# main_full_32.net
KiCad netlist of a schematic drawn in EAGLE
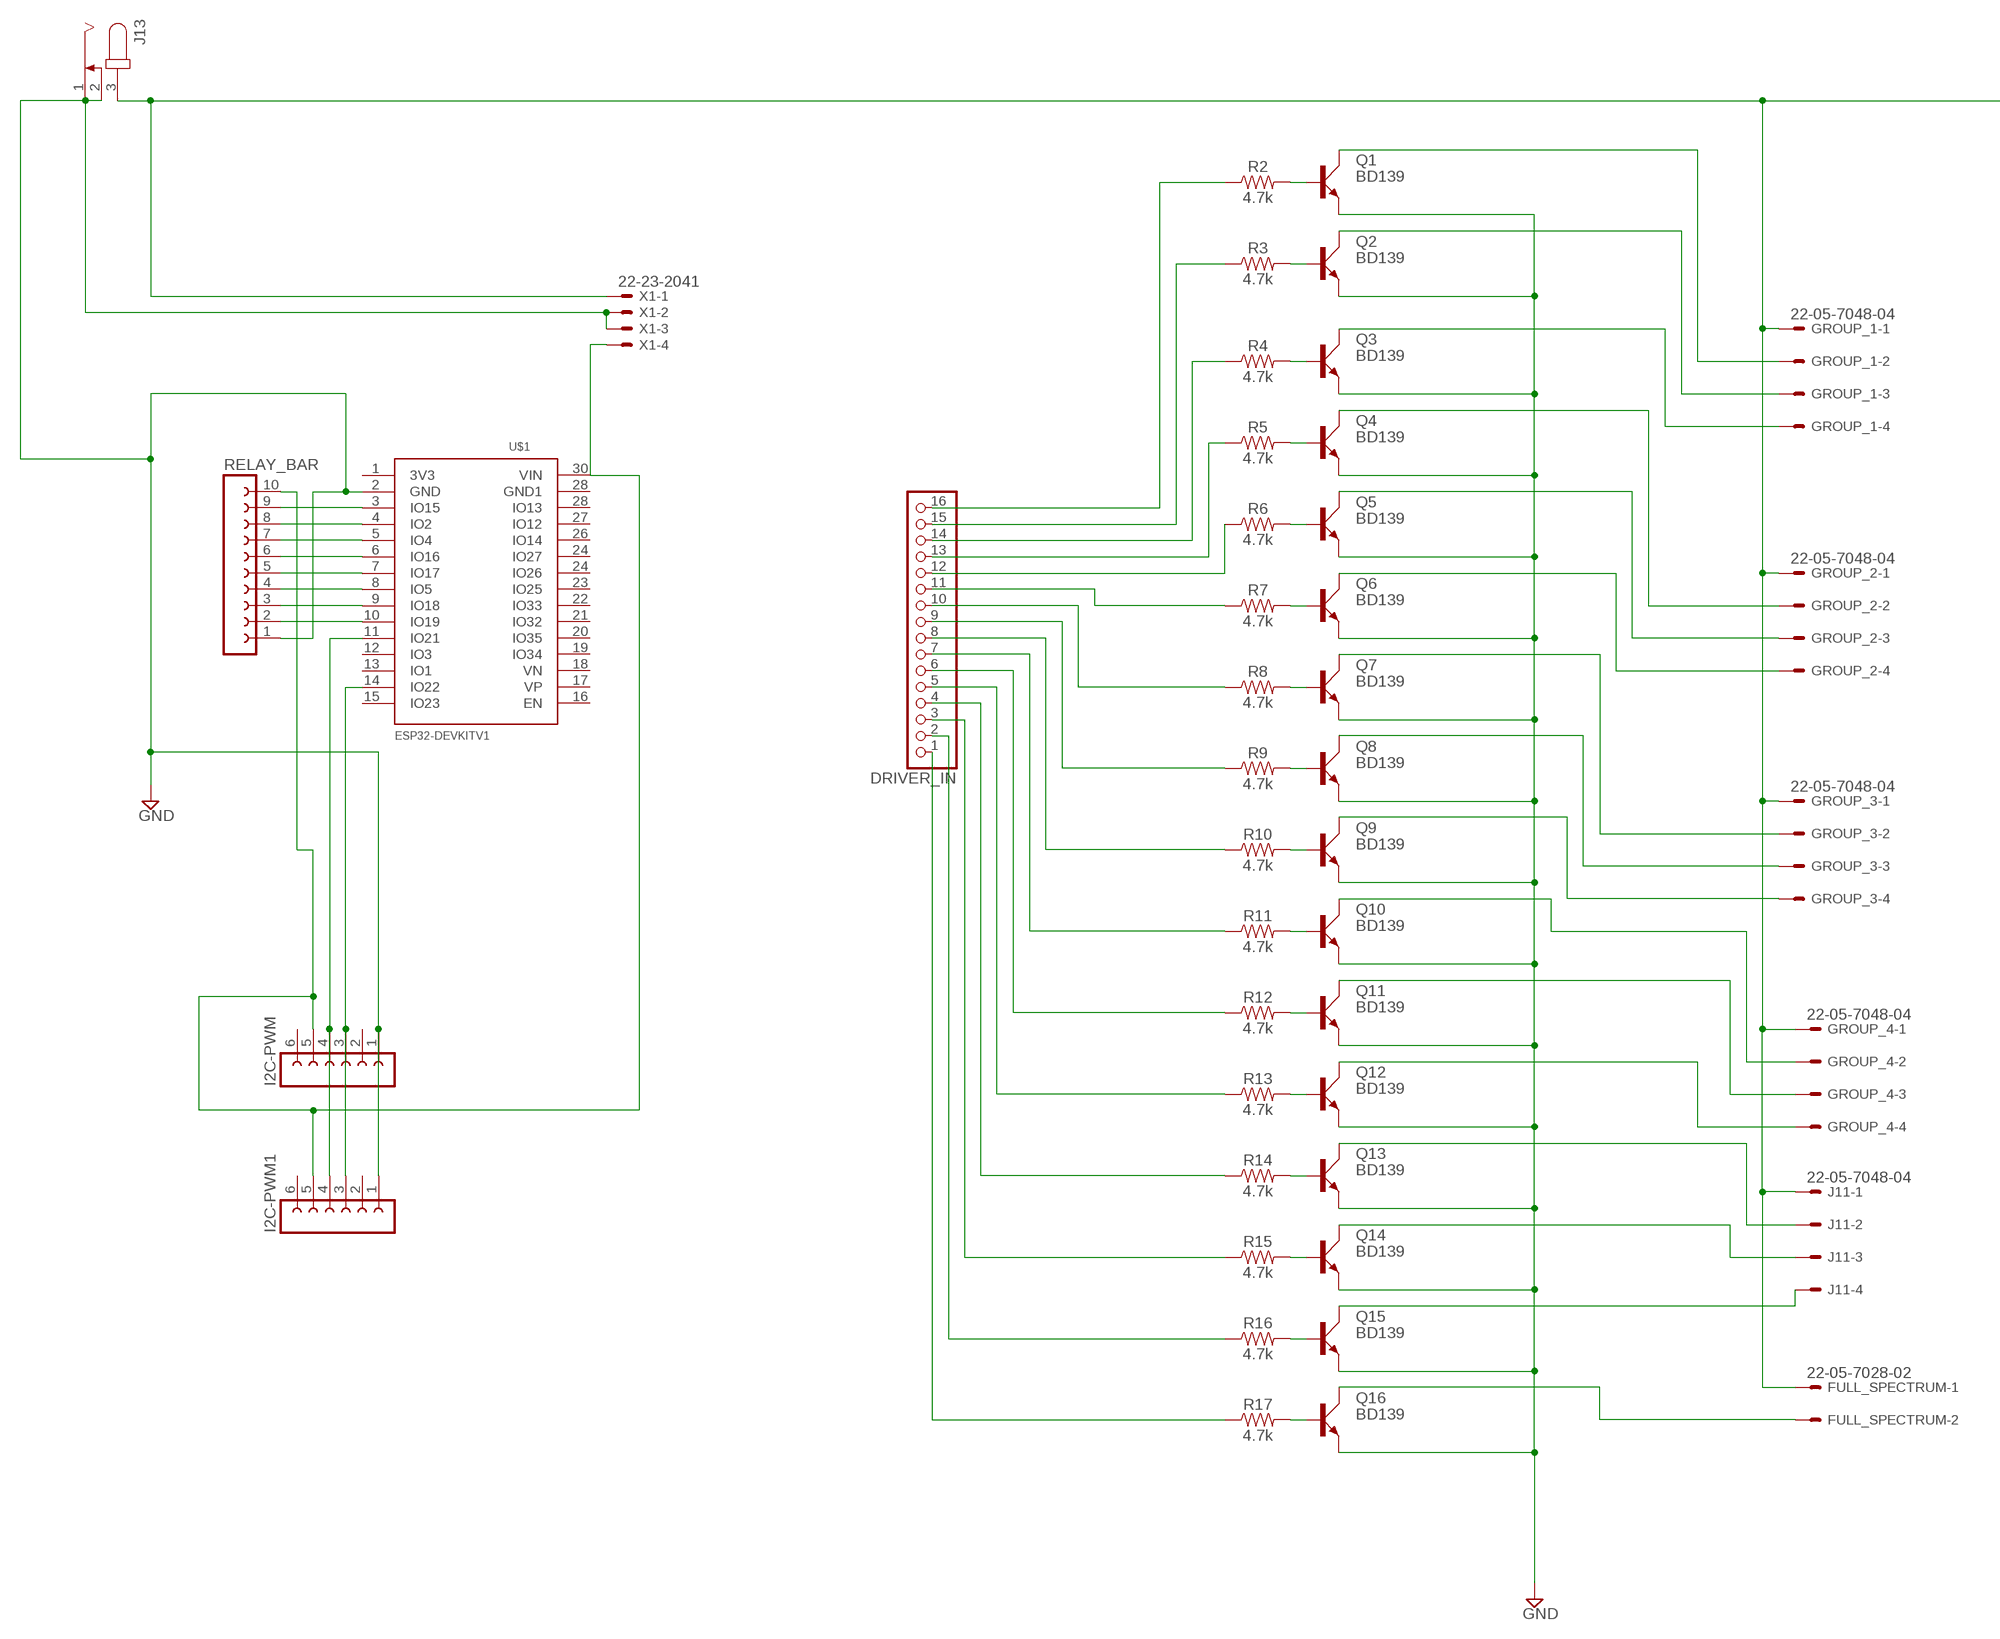
[diagram p0: schematic, sheet 1, part 1 of 2]
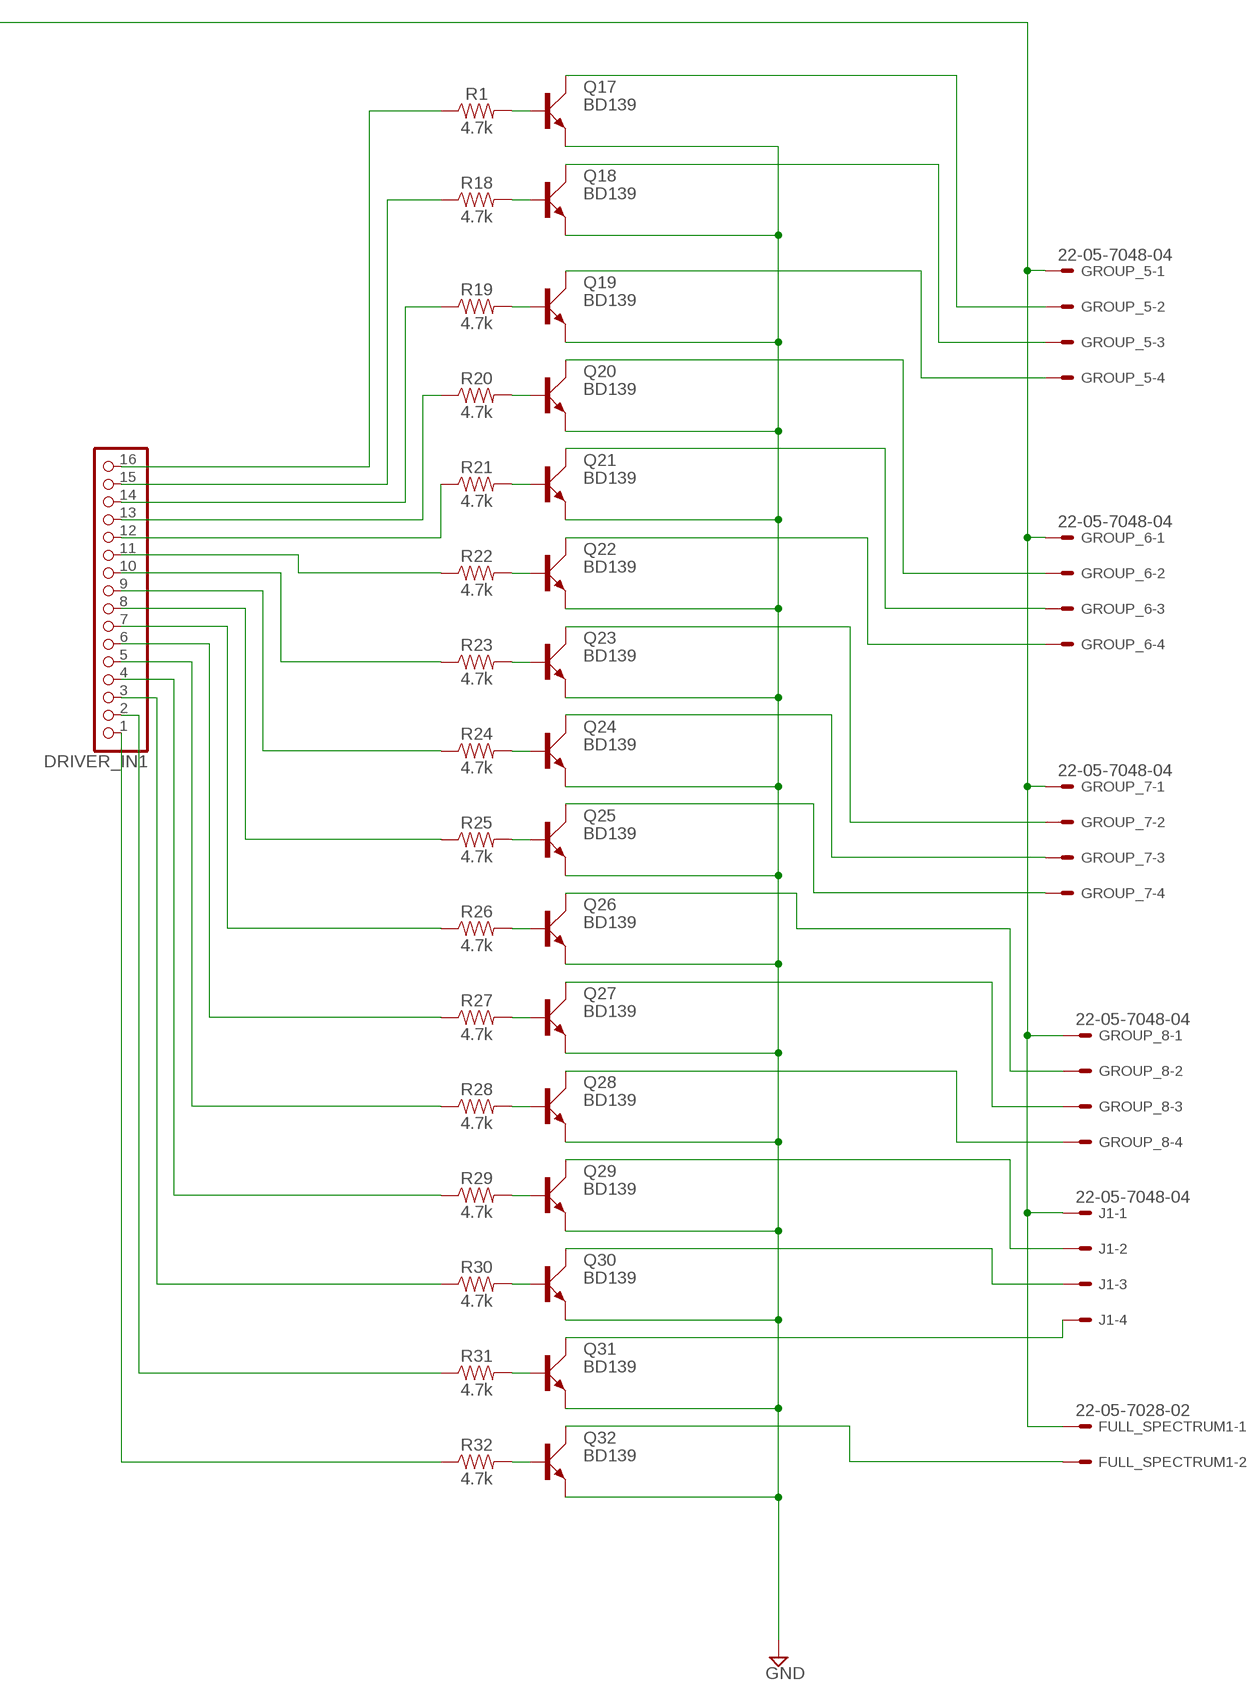
[diagram p1: schematic, sheet 1, part 2 of 2]

(export (version "E")
  (design (tool "Eeschema 10.0.6"))
  (components
    (comp (ref "DRIVER_IN")
      (value "PINHD-1X16/90")
      (footprint "eagle-import:1X16_90")
      (libsource (lib "eagle-import") (part "PINHD-1X16/90"))
    )
    (comp (ref "DRIVER_IN1")
      (value "PINHD-1X16/90")
      (footprint "eagle-import:1X16_90")
      (libsource (lib "eagle-import") (part "PINHD-1X16/90"))
    )
    (comp (ref "FULL_SPECTRUM")
      (value "22-05-7028-02")
      (footprint "eagle-import:7395-02")
      (fields (field (name "MF") "MOLEX"))
      (libsource (lib "eagle-import") (part "22-?-0205-7028"))
    )
    (comp (ref "FULL_SPECTRUM1")
      (value "22-05-7028-02")
      (footprint "eagle-import:7395-02")
      (fields (field (name "MF") "MOLEX"))
      (libsource (lib "eagle-import") (part "22-?-0205-7028"))
    )
    (comp (ref "GROUP_1")
      (value "22-05-7048-04")
      (footprint "eagle-import:7395-04")
      (fields (field (name "MF") "MOLEX"))
      (libsource (lib "eagle-import") (part "22-?-0405-7048"))
    )
    (comp (ref "GROUP_2")
      (value "22-05-7048-04")
      (footprint "eagle-import:7395-04")
      (fields (field (name "MF") "MOLEX"))
      (libsource (lib "eagle-import") (part "22-?-0405-7048"))
    )
    (comp (ref "GROUP_3")
      (value "22-05-7048-04")
      (footprint "eagle-import:7395-04")
      (fields (field (name "MF") "MOLEX"))
      (libsource (lib "eagle-import") (part "22-?-0405-7048"))
    )
    (comp (ref "GROUP_4")
      (value "22-05-7048-04")
      (footprint "eagle-import:7395-04")
      (fields (field (name "MF") "MOLEX"))
      (libsource (lib "eagle-import") (part "22-?-0405-7048"))
    )
    (comp (ref "GROUP_5")
      (value "22-05-7048-04")
      (footprint "eagle-import:7395-04")
      (fields (field (name "MF") "MOLEX"))
      (libsource (lib "eagle-import") (part "22-?-0405-7048"))
    )
    (comp (ref "GROUP_6")
      (value "22-05-7048-04")
      (footprint "eagle-import:7395-04")
      (fields (field (name "MF") "MOLEX"))
      (libsource (lib "eagle-import") (part "22-?-0405-7048"))
    )
    (comp (ref "GROUP_7")
      (value "22-05-7048-04")
      (footprint "eagle-import:7395-04")
      (fields (field (name "MF") "MOLEX"))
      (libsource (lib "eagle-import") (part "22-?-0405-7048"))
    )
    (comp (ref "GROUP_8")
      (value "22-05-7048-04")
      (footprint "eagle-import:7395-04")
      (fields (field (name "MF") "MOLEX"))
      (libsource (lib "eagle-import") (part "22-?-0405-7048"))
    )
    (comp (ref "I2C-PWM")
      (value "FE06W")
      (footprint "eagle-import:FE06W")
      (libsource (lib "eagle-import") (part "FE06W"))
    )
    (comp (ref "I2C-PWM1")
      (value "FE06W")
      (footprint "eagle-import:FE06W")
      (libsource (lib "eagle-import") (part "FE06W"))
    )
    (comp (ref "J1")
      (value "22-05-7048-04")
      (footprint "eagle-import:7395-04")
      (fields (field (name "MF") "MOLEX"))
      (libsource (lib "eagle-import") (part "22-?-0405-7048"))
    )
    (comp (ref "J11")
      (value "22-05-7048-04")
      (footprint "eagle-import:7395-04")
      (fields (field (name "MF") "MOLEX"))
      (libsource (lib "eagle-import") (part "22-?-0405-7048"))
    )
    (comp (ref "J13")
      (value "JACK-PLUG0")
      (footprint "eagle-import:SPC4077")
      (libsource (lib "eagle-import") (part "JACK-PLUG0"))
    )
    (comp (ref "Q1")
      (value "BD139")
      (footprint "eagle-import:TO126AV")
      (libsource (lib "eagle-import") (part "BD139"))
    )
    (comp (ref "Q2")
      (value "BD139")
      (footprint "eagle-import:TO126AV")
      (libsource (lib "eagle-import") (part "BD139"))
    )
    (comp (ref "Q3")
      (value "BD139")
      (footprint "eagle-import:TO126AV")
      (libsource (lib "eagle-import") (part "BD139"))
    )
    (comp (ref "Q4")
      (value "BD139")
      (footprint "eagle-import:TO126AV")
      (libsource (lib "eagle-import") (part "BD139"))
    )
    (comp (ref "Q5")
      (value "BD139")
      (footprint "eagle-import:TO126AV")
      (libsource (lib "eagle-import") (part "BD139"))
    )
    (comp (ref "Q6")
      (value "BD139")
      (footprint "eagle-import:TO126AV")
      (libsource (lib "eagle-import") (part "BD139"))
    )
    (comp (ref "Q7")
      (value "BD139")
      (footprint "eagle-import:TO126AV")
      (libsource (lib "eagle-import") (part "BD139"))
    )
    (comp (ref "Q8")
      (value "BD139")
      (footprint "eagle-import:TO126AV")
      (libsource (lib "eagle-import") (part "BD139"))
    )
    (comp (ref "Q9")
      (value "BD139")
      (footprint "eagle-import:TO126AV")
      (libsource (lib "eagle-import") (part "BD139"))
    )
    (comp (ref "Q10")
      (value "BD139")
      (footprint "eagle-import:TO126AV")
      (libsource (lib "eagle-import") (part "BD139"))
    )
    (comp (ref "Q11")
      (value "BD139")
      (footprint "eagle-import:TO126AV")
      (libsource (lib "eagle-import") (part "BD139"))
    )
    (comp (ref "Q12")
      (value "BD139")
      (footprint "eagle-import:TO126AV")
      (libsource (lib "eagle-import") (part "BD139"))
    )
    (comp (ref "Q13")
      (value "BD139")
      (footprint "eagle-import:TO126AV")
      (libsource (lib "eagle-import") (part "BD139"))
    )
    (comp (ref "Q14")
      (value "BD139")
      (footprint "eagle-import:TO126AV")
      (libsource (lib "eagle-import") (part "BD139"))
    )
    (comp (ref "Q15")
      (value "BD139")
      (footprint "eagle-import:TO126AV")
      (libsource (lib "eagle-import") (part "BD139"))
    )
    (comp (ref "Q16")
      (value "BD139")
      (footprint "eagle-import:TO126AV")
      (libsource (lib "eagle-import") (part "BD139"))
    )
    (comp (ref "Q17")
      (value "BD139")
      (footprint "eagle-import:TO126AV")
      (libsource (lib "eagle-import") (part "BD139"))
    )
    (comp (ref "Q18")
      (value "BD139")
      (footprint "eagle-import:TO126AV")
      (libsource (lib "eagle-import") (part "BD139"))
    )
    (comp (ref "Q19")
      (value "BD139")
      (footprint "eagle-import:TO126AV")
      (libsource (lib "eagle-import") (part "BD139"))
    )
    (comp (ref "Q20")
      (value "BD139")
      (footprint "eagle-import:TO126AV")
      (libsource (lib "eagle-import") (part "BD139"))
    )
    (comp (ref "Q21")
      (value "BD139")
      (footprint "eagle-import:TO126AV")
      (libsource (lib "eagle-import") (part "BD139"))
    )
    (comp (ref "Q22")
      (value "BD139")
      (footprint "eagle-import:TO126AV")
      (libsource (lib "eagle-import") (part "BD139"))
    )
    (comp (ref "Q23")
      (value "BD139")
      (footprint "eagle-import:TO126AV")
      (libsource (lib "eagle-import") (part "BD139"))
    )
    (comp (ref "Q24")
      (value "BD139")
      (footprint "eagle-import:TO126AV")
      (libsource (lib "eagle-import") (part "BD139"))
    )
    (comp (ref "Q25")
      (value "BD139")
      (footprint "eagle-import:TO126AV")
      (libsource (lib "eagle-import") (part "BD139"))
    )
    (comp (ref "Q26")
      (value "BD139")
      (footprint "eagle-import:TO126AV")
      (libsource (lib "eagle-import") (part "BD139"))
    )
    (comp (ref "Q27")
      (value "BD139")
      (footprint "eagle-import:TO126AV")
      (libsource (lib "eagle-import") (part "BD139"))
    )
    (comp (ref "Q28")
      (value "BD139")
      (footprint "eagle-import:TO126AV")
      (libsource (lib "eagle-import") (part "BD139"))
    )
    (comp (ref "Q29")
      (value "BD139")
      (footprint "eagle-import:TO126AV")
      (libsource (lib "eagle-import") (part "BD139"))
    )
    (comp (ref "Q30")
      (value "BD139")
      (footprint "eagle-import:TO126AV")
      (libsource (lib "eagle-import") (part "BD139"))
    )
    (comp (ref "Q31")
      (value "BD139")
      (footprint "eagle-import:TO126AV")
      (libsource (lib "eagle-import") (part "BD139"))
    )
    (comp (ref "Q32")
      (value "BD139")
      (footprint "eagle-import:TO126AV")
      (libsource (lib "eagle-import") (part "BD139"))
    )
    (comp (ref "R1")
      (value "4.7k")
      (footprint "eagle-import:0603")
      (libsource (lib "eagle-import") (part "4.7KOHM-0603-1/10W-1%"))
    )
    (comp (ref "R2")
      (value "4.7k")
      (footprint "eagle-import:0603")
      (libsource (lib "eagle-import") (part "4.7KOHM-0603-1/10W-1%"))
    )
    (comp (ref "R3")
      (value "4.7k")
      (footprint "eagle-import:0603")
      (libsource (lib "eagle-import") (part "4.7KOHM-0603-1/10W-1%"))
    )
    (comp (ref "R4")
      (value "4.7k")
      (footprint "eagle-import:0603")
      (libsource (lib "eagle-import") (part "4.7KOHM-0603-1/10W-1%"))
    )
    (comp (ref "R5")
      (value "4.7k")
      (footprint "eagle-import:0603")
      (libsource (lib "eagle-import") (part "4.7KOHM-0603-1/10W-1%"))
    )
    (comp (ref "R6")
      (value "4.7k")
      (footprint "eagle-import:0603")
      (libsource (lib "eagle-import") (part "4.7KOHM-0603-1/10W-1%"))
    )
    (comp (ref "R7")
      (value "4.7k")
      (footprint "eagle-import:0603")
      (libsource (lib "eagle-import") (part "4.7KOHM-0603-1/10W-1%"))
    )
    (comp (ref "R8")
      (value "4.7k")
      (footprint "eagle-import:0603")
      (libsource (lib "eagle-import") (part "4.7KOHM-0603-1/10W-1%"))
    )
    (comp (ref "R9")
      (value "4.7k")
      (footprint "eagle-import:0603")
      (libsource (lib "eagle-import") (part "4.7KOHM-0603-1/10W-1%"))
    )
    (comp (ref "R10")
      (value "4.7k")
      (footprint "eagle-import:0603")
      (libsource (lib "eagle-import") (part "4.7KOHM-0603-1/10W-1%"))
    )
    (comp (ref "R11")
      (value "4.7k")
      (footprint "eagle-import:0603")
      (libsource (lib "eagle-import") (part "4.7KOHM-0603-1/10W-1%"))
    )
    (comp (ref "R12")
      (value "4.7k")
      (footprint "eagle-import:0603")
      (libsource (lib "eagle-import") (part "4.7KOHM-0603-1/10W-1%"))
    )
    (comp (ref "R13")
      (value "4.7k")
      (footprint "eagle-import:0603")
      (libsource (lib "eagle-import") (part "4.7KOHM-0603-1/10W-1%"))
    )
    (comp (ref "R14")
      (value "4.7k")
      (footprint "eagle-import:0603")
      (libsource (lib "eagle-import") (part "4.7KOHM-0603-1/10W-1%"))
    )
    (comp (ref "R15")
      (value "4.7k")
      (footprint "eagle-import:0603")
      (libsource (lib "eagle-import") (part "4.7KOHM-0603-1/10W-1%"))
    )
    (comp (ref "R16")
      (value "4.7k")
      (footprint "eagle-import:0603")
      (libsource (lib "eagle-import") (part "4.7KOHM-0603-1/10W-1%"))
    )
    (comp (ref "R17")
      (value "4.7k")
      (footprint "eagle-import:0603")
      (libsource (lib "eagle-import") (part "4.7KOHM-0603-1/10W-1%"))
    )
    (comp (ref "R18")
      (value "4.7k")
      (footprint "eagle-import:0603")
      (libsource (lib "eagle-import") (part "4.7KOHM-0603-1/10W-1%"))
    )
    (comp (ref "R19")
      (value "4.7k")
      (footprint "eagle-import:0603")
      (libsource (lib "eagle-import") (part "4.7KOHM-0603-1/10W-1%"))
    )
    (comp (ref "R20")
      (value "4.7k")
      (footprint "eagle-import:0603")
      (libsource (lib "eagle-import") (part "4.7KOHM-0603-1/10W-1%"))
    )
    (comp (ref "R21")
      (value "4.7k")
      (footprint "eagle-import:0603")
      (libsource (lib "eagle-import") (part "4.7KOHM-0603-1/10W-1%"))
    )
    (comp (ref "R22")
      (value "4.7k")
      (footprint "eagle-import:0603")
      (libsource (lib "eagle-import") (part "4.7KOHM-0603-1/10W-1%"))
    )
    (comp (ref "R23")
      (value "4.7k")
      (footprint "eagle-import:0603")
      (libsource (lib "eagle-import") (part "4.7KOHM-0603-1/10W-1%"))
    )
    (comp (ref "R24")
      (value "4.7k")
      (footprint "eagle-import:0603")
      (libsource (lib "eagle-import") (part "4.7KOHM-0603-1/10W-1%"))
    )
    (comp (ref "R25")
      (value "4.7k")
      (footprint "eagle-import:0603")
      (libsource (lib "eagle-import") (part "4.7KOHM-0603-1/10W-1%"))
    )
    (comp (ref "R26")
      (value "4.7k")
      (footprint "eagle-import:0603")
      (libsource (lib "eagle-import") (part "4.7KOHM-0603-1/10W-1%"))
    )
    (comp (ref "R27")
      (value "4.7k")
      (footprint "eagle-import:0603")
      (libsource (lib "eagle-import") (part "4.7KOHM-0603-1/10W-1%"))
    )
    (comp (ref "R28")
      (value "4.7k")
      (footprint "eagle-import:0603")
      (libsource (lib "eagle-import") (part "4.7KOHM-0603-1/10W-1%"))
    )
    (comp (ref "R29")
      (value "4.7k")
      (footprint "eagle-import:0603")
      (libsource (lib "eagle-import") (part "4.7KOHM-0603-1/10W-1%"))
    )
    (comp (ref "R30")
      (value "4.7k")
      (footprint "eagle-import:0603")
      (libsource (lib "eagle-import") (part "4.7KOHM-0603-1/10W-1%"))
    )
    (comp (ref "R31")
      (value "4.7k")
      (footprint "eagle-import:0603")
      (libsource (lib "eagle-import") (part "4.7KOHM-0603-1/10W-1%"))
    )
    (comp (ref "R32")
      (value "4.7k")
      (footprint "eagle-import:0603")
      (libsource (lib "eagle-import") (part "4.7KOHM-0603-1/10W-1%"))
    )
    (comp (ref "RELAY_BAR")
      (value "FE10W")
      (footprint "eagle-import:FE10W")
      (libsource (lib "eagle-import") (part "FE10W"))
    )
    (comp (ref "U$1")
      (value "ESP32DEVKITV1")
      (footprint "eagle-import:ESP32-DEVKITV1")
      (libsource (lib "eagle-import") (part "ESP32DEVKITV1"))
    )
    (comp (ref "X1")
      (value "22-23-2041")
      (footprint "eagle-import:22-23-2041")
      (fields (field (name "MF") "MOLEX"))
      (libsource (lib "eagle-import") (part "22-23-2041"))
    )
  )
  (nets
    (net (code "1") (name "GND") (class "Default")
      (node (ref "I2C-PWM") (pin "1") (pinfunction "1_1") (pintype "passive"))
      (node (ref "I2C-PWM1") (pin "1") (pinfunction "1_1") (pintype "passive"))
      (node (ref "J13") (pin "1") (pinfunction "1_1") (pintype "passive"))
      (node (ref "J13") (pin "2") (pinfunction "2_2") (pintype "passive"))
      (node (ref "Q1") (pin "E") (pinfunction "E_E") (pintype "passive"))
      (node (ref "Q10") (pin "E") (pinfunction "E_E") (pintype "passive"))
      (node (ref "Q11") (pin "E") (pinfunction "E_E") (pintype "passive"))
      (node (ref "Q12") (pin "E") (pinfunction "E_E") (pintype "passive"))
      (node (ref "Q13") (pin "E") (pinfunction "E_E") (pintype "passive"))
      (node (ref "Q14") (pin "E") (pinfunction "E_E") (pintype "passive"))
      (node (ref "Q15") (pin "E") (pinfunction "E_E") (pintype "passive"))
      (node (ref "Q16") (pin "E") (pinfunction "E_E") (pintype "passive"))
      (node (ref "Q17") (pin "E") (pinfunction "E_E") (pintype "passive"))
      (node (ref "Q18") (pin "E") (pinfunction "E_E") (pintype "passive"))
      (node (ref "Q19") (pin "E") (pinfunction "E_E") (pintype "passive"))
      (node (ref "Q2") (pin "E") (pinfunction "E_E") (pintype "passive"))
      (node (ref "Q20") (pin "E") (pinfunction "E_E") (pintype "passive"))
      (node (ref "Q21") (pin "E") (pinfunction "E_E") (pintype "passive"))
      (node (ref "Q22") (pin "E") (pinfunction "E_E") (pintype "passive"))
      (node (ref "Q23") (pin "E") (pinfunction "E_E") (pintype "passive"))
      (node (ref "Q24") (pin "E") (pinfunction "E_E") (pintype "passive"))
      (node (ref "Q25") (pin "E") (pinfunction "E_E") (pintype "passive"))
      (node (ref "Q26") (pin "E") (pinfunction "E_E") (pintype "passive"))
      (node (ref "Q27") (pin "E") (pinfunction "E_E") (pintype "passive"))
      (node (ref "Q28") (pin "E") (pinfunction "E_E") (pintype "passive"))
      (node (ref "Q29") (pin "E") (pinfunction "E_E") (pintype "passive"))
      (node (ref "Q3") (pin "E") (pinfunction "E_E") (pintype "passive"))
      (node (ref "Q30") (pin "E") (pinfunction "E_E") (pintype "passive"))
      (node (ref "Q31") (pin "E") (pinfunction "E_E") (pintype "passive"))
      (node (ref "Q32") (pin "E") (pinfunction "E_E") (pintype "passive"))
      (node (ref "Q4") (pin "E") (pinfunction "E_E") (pintype "passive"))
      (node (ref "Q5") (pin "E") (pinfunction "E_E") (pintype "passive"))
      (node (ref "Q6") (pin "E") (pinfunction "E_E") (pintype "passive"))
      (node (ref "Q7") (pin "E") (pinfunction "E_E") (pintype "passive"))
      (node (ref "Q8") (pin "E") (pinfunction "E_E") (pintype "passive"))
      (node (ref "Q9") (pin "E") (pinfunction "E_E") (pintype "passive"))
      (node (ref "RELAY_BAR") (pin "1") (pinfunction "1_1") (pintype "passive"))
      (node (ref "U$1") (pin "2") (pinfunction "GND_2") (pintype "bidirectional"))
      (node (ref "X1") (pin "2") (pinfunction "S_2") (pintype "passive"))
      (node (ref "X1") (pin "3") (pinfunction "S_3") (pintype "passive"))
    )
    (net (code "2") (name "Net-(DRIVER_IN-Pad1)") (class "Default")
      (node (ref "DRIVER_IN") (pin "1") (pinfunction "1_1") (pintype "passive"))
      (node (ref "R17") (pin "1") (pinfunction "1_1") (pintype "passive"))
    )
    (net (code "3") (name "Net-(DRIVER_IN-Pad2)") (class "Default")
      (node (ref "DRIVER_IN") (pin "2") (pinfunction "2_2") (pintype "passive"))
      (node (ref "R16") (pin "1") (pinfunction "1_1") (pintype "passive"))
    )
    (net (code "4") (name "Net-(DRIVER_IN-Pad3)") (class "Default")
      (node (ref "DRIVER_IN") (pin "3") (pinfunction "3_3") (pintype "passive"))
      (node (ref "R15") (pin "1") (pinfunction "1_1") (pintype "passive"))
    )
    (net (code "5") (name "Net-(DRIVER_IN-Pad4)") (class "Default")
      (node (ref "DRIVER_IN") (pin "4") (pinfunction "4_4") (pintype "passive"))
      (node (ref "R14") (pin "1") (pinfunction "1_1") (pintype "passive"))
    )
    (net (code "6") (name "Net-(DRIVER_IN-Pad5)") (class "Default")
      (node (ref "DRIVER_IN") (pin "5") (pinfunction "5_5") (pintype "passive"))
      (node (ref "R13") (pin "1") (pinfunction "1_1") (pintype "passive"))
    )
    (net (code "7") (name "Net-(DRIVER_IN-Pad6)") (class "Default")
      (node (ref "DRIVER_IN") (pin "6") (pinfunction "6_6") (pintype "passive"))
      (node (ref "R12") (pin "1") (pinfunction "1_1") (pintype "passive"))
    )
    (net (code "8") (name "Net-(DRIVER_IN-Pad7)") (class "Default")
      (node (ref "DRIVER_IN") (pin "7") (pinfunction "7_7") (pintype "passive"))
      (node (ref "R11") (pin "1") (pinfunction "1_1") (pintype "passive"))
    )
    (net (code "9") (name "Net-(DRIVER_IN-Pad8)") (class "Default")
      (node (ref "DRIVER_IN") (pin "8") (pinfunction "8_8") (pintype "passive"))
      (node (ref "R10") (pin "1") (pinfunction "1_1") (pintype "passive"))
    )
    (net (code "10") (name "Net-(DRIVER_IN-Pad9)") (class "Default")
      (node (ref "DRIVER_IN") (pin "9") (pinfunction "9_9") (pintype "passive"))
      (node (ref "R9") (pin "1") (pinfunction "1_1") (pintype "passive"))
    )
    (net (code "11") (name "Net-(DRIVER_IN-Pad10)") (class "Default")
      (node (ref "DRIVER_IN") (pin "10") (pinfunction "10_10") (pintype "passive"))
      (node (ref "R8") (pin "1") (pinfunction "1_1") (pintype "passive"))
    )
    (net (code "12") (name "Net-(DRIVER_IN-Pad11)") (class "Default")
      (node (ref "DRIVER_IN") (pin "11") (pinfunction "11_11") (pintype "passive"))
      (node (ref "R7") (pin "1") (pinfunction "1_1") (pintype "passive"))
    )
    (net (code "13") (name "Net-(DRIVER_IN-Pad12)") (class "Default")
      (node (ref "DRIVER_IN") (pin "12") (pinfunction "12_12") (pintype "passive"))
      (node (ref "R6") (pin "1") (pinfunction "1_1") (pintype "passive"))
    )
    (net (code "14") (name "Net-(DRIVER_IN-Pad13)") (class "Default")
      (node (ref "DRIVER_IN") (pin "13") (pinfunction "13_13") (pintype "passive"))
      (node (ref "R5") (pin "1") (pinfunction "1_1") (pintype "passive"))
    )
    (net (code "15") (name "Net-(DRIVER_IN-Pad14)") (class "Default")
      (node (ref "DRIVER_IN") (pin "14") (pinfunction "14_14") (pintype "passive"))
      (node (ref "R4") (pin "1") (pinfunction "1_1") (pintype "passive"))
    )
    (net (code "16") (name "Net-(DRIVER_IN-Pad15)") (class "Default")
      (node (ref "DRIVER_IN") (pin "15") (pinfunction "15_15") (pintype "passive"))
      (node (ref "R3") (pin "1") (pinfunction "1_1") (pintype "passive"))
    )
    (net (code "17") (name "Net-(DRIVER_IN-Pad16)") (class "Default")
      (node (ref "DRIVER_IN") (pin "16") (pinfunction "16_16") (pintype "passive"))
      (node (ref "R2") (pin "1") (pinfunction "1_1") (pintype "passive"))
    )
    (net (code "18") (name "Net-(DRIVER_IN1-Pad1)") (class "Default")
      (node (ref "DRIVER_IN1") (pin "1") (pinfunction "1_1") (pintype "passive"))
      (node (ref "R32") (pin "1") (pinfunction "1_1") (pintype "passive"))
    )
    (net (code "19") (name "Net-(DRIVER_IN1-Pad2)") (class "Default")
      (node (ref "DRIVER_IN1") (pin "2") (pinfunction "2_2") (pintype "passive"))
      (node (ref "R31") (pin "1") (pinfunction "1_1") (pintype "passive"))
    )
    (net (code "20") (name "Net-(DRIVER_IN1-Pad3)") (class "Default")
      (node (ref "DRIVER_IN1") (pin "3") (pinfunction "3_3") (pintype "passive"))
      (node (ref "R30") (pin "1") (pinfunction "1_1") (pintype "passive"))
    )
    (net (code "21") (name "Net-(DRIVER_IN1-Pad4)") (class "Default")
      (node (ref "DRIVER_IN1") (pin "4") (pinfunction "4_4") (pintype "passive"))
      (node (ref "R29") (pin "1") (pinfunction "1_1") (pintype "passive"))
    )
    (net (code "22") (name "Net-(DRIVER_IN1-Pad5)") (class "Default")
      (node (ref "DRIVER_IN1") (pin "5") (pinfunction "5_5") (pintype "passive"))
      (node (ref "R28") (pin "1") (pinfunction "1_1") (pintype "passive"))
    )
    (net (code "23") (name "Net-(DRIVER_IN1-Pad6)") (class "Default")
      (node (ref "DRIVER_IN1") (pin "6") (pinfunction "6_6") (pintype "passive"))
      (node (ref "R27") (pin "1") (pinfunction "1_1") (pintype "passive"))
    )
    (net (code "24") (name "Net-(DRIVER_IN1-Pad7)") (class "Default")
      (node (ref "DRIVER_IN1") (pin "7") (pinfunction "7_7") (pintype "passive"))
      (node (ref "R26") (pin "1") (pinfunction "1_1") (pintype "passive"))
    )
    (net (code "25") (name "Net-(DRIVER_IN1-Pad8)") (class "Default")
      (node (ref "DRIVER_IN1") (pin "8") (pinfunction "8_8") (pintype "passive"))
      (node (ref "R25") (pin "1") (pinfunction "1_1") (pintype "passive"))
    )
    (net (code "26") (name "Net-(DRIVER_IN1-Pad9)") (class "Default")
      (node (ref "DRIVER_IN1") (pin "9") (pinfunction "9_9") (pintype "passive"))
      (node (ref "R24") (pin "1") (pinfunction "1_1") (pintype "passive"))
    )
    (net (code "27") (name "Net-(DRIVER_IN1-Pad10)") (class "Default")
      (node (ref "DRIVER_IN1") (pin "10") (pinfunction "10_10") (pintype "passive"))
      (node (ref "R23") (pin "1") (pinfunction "1_1") (pintype "passive"))
    )
    (net (code "28") (name "Net-(DRIVER_IN1-Pad11)") (class "Default")
      (node (ref "DRIVER_IN1") (pin "11") (pinfunction "11_11") (pintype "passive"))
      (node (ref "R22") (pin "1") (pinfunction "1_1") (pintype "passive"))
    )
    (net (code "29") (name "Net-(DRIVER_IN1-Pad12)") (class "Default")
      (node (ref "DRIVER_IN1") (pin "12") (pinfunction "12_12") (pintype "passive"))
      (node (ref "R21") (pin "1") (pinfunction "1_1") (pintype "passive"))
    )
    (net (code "30") (name "Net-(DRIVER_IN1-Pad13)") (class "Default")
      (node (ref "DRIVER_IN1") (pin "13") (pinfunction "13_13") (pintype "passive"))
      (node (ref "R20") (pin "1") (pinfunction "1_1") (pintype "passive"))
    )
    (net (code "31") (name "Net-(DRIVER_IN1-Pad14)") (class "Default")
      (node (ref "DRIVER_IN1") (pin "14") (pinfunction "14_14") (pintype "passive"))
      (node (ref "R19") (pin "1") (pinfunction "1_1") (pintype "passive"))
    )
    (net (code "32") (name "Net-(DRIVER_IN1-Pad15)") (class "Default")
      (node (ref "DRIVER_IN1") (pin "15") (pinfunction "15_15") (pintype "passive"))
      (node (ref "R18") (pin "1") (pinfunction "1_1") (pintype "passive"))
    )
    (net (code "33") (name "Net-(DRIVER_IN1-Pad16)") (class "Default")
      (node (ref "DRIVER_IN1") (pin "16") (pinfunction "16_16") (pintype "passive"))
      (node (ref "R1") (pin "1") (pinfunction "1_1") (pintype "passive"))
    )
    (net (code "34") (name "Net-(FULL_SPECTRUM1A-S)") (class "Default")
      (node (ref "FULL_SPECTRUM") (pin "1") (pinfunction "S_1") (pintype "passive"))
      (node (ref "FULL_SPECTRUM1") (pin "1") (pinfunction "S_1") (pintype "passive"))
      (node (ref "GROUP_1") (pin "1") (pinfunction "S_1") (pintype "passive"))
      (node (ref "GROUP_2") (pin "1") (pinfunction "S_1") (pintype "passive"))
      (node (ref "GROUP_3") (pin "1") (pinfunction "S_1") (pintype "passive"))
      (node (ref "GROUP_4") (pin "1") (pinfunction "S_1") (pintype "passive"))
      (node (ref "GROUP_5") (pin "1") (pinfunction "S_1") (pintype "passive"))
      (node (ref "GROUP_6") (pin "1") (pinfunction "S_1") (pintype "passive"))
      (node (ref "GROUP_7") (pin "1") (pinfunction "S_1") (pintype "passive"))
      (node (ref "GROUP_8") (pin "1") (pinfunction "S_1") (pintype "passive"))
      (node (ref "J1") (pin "1") (pinfunction "S_1") (pintype "passive"))
      (node (ref "J11") (pin "1") (pinfunction "S_1") (pintype "passive"))
      (node (ref "J13") (pin "3") (pinfunction "3_3") (pintype "passive"))
      (node (ref "X1") (pin "1") (pinfunction "S_1") (pintype "passive"))
    )
    (net (code "35") (name "Net-(FULL_SPECTRUM1B-S)") (class "Default")
      (node (ref "FULL_SPECTRUM1") (pin "2") (pinfunction "S_2") (pintype "passive"))
      (node (ref "Q32") (pin "C") (pinfunction "C_C") (pintype "passive"))
    )
    (net (code "36") (name "Net-(FULL_SPECTRUMB-S)") (class "Default")
      (node (ref "FULL_SPECTRUM") (pin "2") (pinfunction "S_2") (pintype "passive"))
      (node (ref "Q16") (pin "C") (pinfunction "C_C") (pintype "passive"))
    )
    (net (code "37") (name "Net-(GROUP_1B-S)") (class "Default")
      (node (ref "GROUP_1") (pin "2") (pinfunction "S_2") (pintype "passive"))
      (node (ref "Q1") (pin "C") (pinfunction "C_C") (pintype "passive"))
    )
    (net (code "38") (name "Net-(GROUP_1C-S)") (class "Default")
      (node (ref "GROUP_1") (pin "3") (pinfunction "S_3") (pintype "passive"))
      (node (ref "Q2") (pin "C") (pinfunction "C_C") (pintype "passive"))
    )
    (net (code "39") (name "Net-(GROUP_1D-S)") (class "Default")
      (node (ref "GROUP_1") (pin "4") (pinfunction "S_4") (pintype "passive"))
      (node (ref "Q3") (pin "C") (pinfunction "C_C") (pintype "passive"))
    )
    (net (code "40") (name "Net-(GROUP_2B-S)") (class "Default")
      (node (ref "GROUP_2") (pin "2") (pinfunction "S_2") (pintype "passive"))
      (node (ref "Q4") (pin "C") (pinfunction "C_C") (pintype "passive"))
    )
    (net (code "41") (name "Net-(GROUP_2C-S)") (class "Default")
      (node (ref "GROUP_2") (pin "3") (pinfunction "S_3") (pintype "passive"))
      (node (ref "Q5") (pin "C") (pinfunction "C_C") (pintype "passive"))
    )
    (net (code "42") (name "Net-(GROUP_2D-S)") (class "Default")
      (node (ref "GROUP_2") (pin "4") (pinfunction "S_4") (pintype "passive"))
      (node (ref "Q6") (pin "C") (pinfunction "C_C") (pintype "passive"))
    )
    (net (code "43") (name "Net-(GROUP_3B-S)") (class "Default")
      (node (ref "GROUP_3") (pin "2") (pinfunction "S_2") (pintype "passive"))
      (node (ref "Q7") (pin "C") (pinfunction "C_C") (pintype "passive"))
    )
    (net (code "44") (name "Net-(GROUP_3C-S)") (class "Default")
      (node (ref "GROUP_3") (pin "3") (pinfunction "S_3") (pintype "passive"))
      (node (ref "Q8") (pin "C") (pinfunction "C_C") (pintype "passive"))
    )
    (net (code "45") (name "Net-(GROUP_3D-S)") (class "Default")
      (node (ref "GROUP_3") (pin "4") (pinfunction "S_4") (pintype "passive"))
      (node (ref "Q9") (pin "C") (pinfunction "C_C") (pintype "passive"))
    )
    (net (code "46") (name "Net-(GROUP_4B-S)") (class "Default")
      (node (ref "GROUP_4") (pin "2") (pinfunction "S_2") (pintype "passive"))
      (node (ref "Q10") (pin "C") (pinfunction "C_C") (pintype "passive"))
    )
    (net (code "47") (name "Net-(GROUP_4C-S)") (class "Default")
      (node (ref "GROUP_4") (pin "3") (pinfunction "S_3") (pintype "passive"))
      (node (ref "Q11") (pin "C") (pinfunction "C_C") (pintype "passive"))
    )
    (net (code "48") (name "Net-(GROUP_4D-S)") (class "Default")
      (node (ref "GROUP_4") (pin "4") (pinfunction "S_4") (pintype "passive"))
      (node (ref "Q12") (pin "C") (pinfunction "C_C") (pintype "passive"))
    )
    (net (code "49") (name "Net-(GROUP_5B-S)") (class "Default")
      (node (ref "GROUP_5") (pin "2") (pinfunction "S_2") (pintype "passive"))
      (node (ref "Q17") (pin "C") (pinfunction "C_C") (pintype "passive"))
    )
    (net (code "50") (name "Net-(GROUP_5C-S)") (class "Default")
      (node (ref "GROUP_5") (pin "3") (pinfunction "S_3") (pintype "passive"))
      (node (ref "Q18") (pin "C") (pinfunction "C_C") (pintype "passive"))
    )
    (net (code "51") (name "Net-(GROUP_5D-S)") (class "Default")
      (node (ref "GROUP_5") (pin "4") (pinfunction "S_4") (pintype "passive"))
      (node (ref "Q19") (pin "C") (pinfunction "C_C") (pintype "passive"))
    )
    (net (code "52") (name "Net-(GROUP_6B-S)") (class "Default")
      (node (ref "GROUP_6") (pin "2") (pinfunction "S_2") (pintype "passive"))
      (node (ref "Q20") (pin "C") (pinfunction "C_C") (pintype "passive"))
    )
    (net (code "53") (name "Net-(GROUP_6C-S)") (class "Default")
      (node (ref "GROUP_6") (pin "3") (pinfunction "S_3") (pintype "passive"))
      (node (ref "Q21") (pin "C") (pinfunction "C_C") (pintype "passive"))
    )
    (net (code "54") (name "Net-(GROUP_6D-S)") (class "Default")
      (node (ref "GROUP_6") (pin "4") (pinfunction "S_4") (pintype "passive"))
      (node (ref "Q22") (pin "C") (pinfunction "C_C") (pintype "passive"))
    )
    (net (code "55") (name "Net-(GROUP_7B-S)") (class "Default")
      (node (ref "GROUP_7") (pin "2") (pinfunction "S_2") (pintype "passive"))
      (node (ref "Q23") (pin "C") (pinfunction "C_C") (pintype "passive"))
    )
    (net (code "56") (name "Net-(GROUP_7C-S)") (class "Default")
      (node (ref "GROUP_7") (pin "3") (pinfunction "S_3") (pintype "passive"))
      (node (ref "Q24") (pin "C") (pinfunction "C_C") (pintype "passive"))
    )
    (net (code "57") (name "Net-(GROUP_7D-S)") (class "Default")
      (node (ref "GROUP_7") (pin "4") (pinfunction "S_4") (pintype "passive"))
      (node (ref "Q25") (pin "C") (pinfunction "C_C") (pintype "passive"))
    )
    (net (code "58") (name "Net-(GROUP_8B-S)") (class "Default")
      (node (ref "GROUP_8") (pin "2") (pinfunction "S_2") (pintype "passive"))
      (node (ref "Q26") (pin "C") (pinfunction "C_C") (pintype "passive"))
    )
    (net (code "59") (name "Net-(GROUP_8C-S)") (class "Default")
      (node (ref "GROUP_8") (pin "3") (pinfunction "S_3") (pintype "passive"))
      (node (ref "Q27") (pin "C") (pinfunction "C_C") (pintype "passive"))
    )
    (net (code "60") (name "Net-(GROUP_8D-S)") (class "Default")
      (node (ref "GROUP_8") (pin "4") (pinfunction "S_4") (pintype "passive"))
      (node (ref "Q28") (pin "C") (pinfunction "C_C") (pintype "passive"))
    )
    (net (code "61") (name "Net-(J1B-S)") (class "Default")
      (node (ref "J1") (pin "2") (pinfunction "S_2") (pintype "passive"))
      (node (ref "Q29") (pin "C") (pinfunction "C_C") (pintype "passive"))
    )
    (net (code "62") (name "Net-(J1C-S)") (class "Default")
      (node (ref "J1") (pin "3") (pinfunction "S_3") (pintype "passive"))
      (node (ref "Q30") (pin "C") (pinfunction "C_C") (pintype "passive"))
    )
    (net (code "63") (name "Net-(J1D-S)") (class "Default")
      (node (ref "J1") (pin "4") (pinfunction "S_4") (pintype "passive"))
      (node (ref "Q31") (pin "C") (pinfunction "C_C") (pintype "passive"))
    )
    (net (code "64") (name "Net-(J11B-S)") (class "Default")
      (node (ref "J11") (pin "2") (pinfunction "S_2") (pintype "passive"))
      (node (ref "Q13") (pin "C") (pinfunction "C_C") (pintype "passive"))
    )
    (net (code "65") (name "Net-(J11C-S)") (class "Default")
      (node (ref "J11") (pin "3") (pinfunction "S_3") (pintype "passive"))
      (node (ref "Q14") (pin "C") (pinfunction "C_C") (pintype "passive"))
    )
    (net (code "66") (name "Net-(J11D-S)") (class "Default")
      (node (ref "J11") (pin "4") (pinfunction "S_4") (pintype "passive"))
      (node (ref "Q15") (pin "C") (pinfunction "C_C") (pintype "passive"))
    )
    (net (code "67") (name "Net-(Q1-PadB)") (class "Default")
      (node (ref "Q1") (pin "B") (pinfunction "B_B") (pintype "passive"))
      (node (ref "R2") (pin "2") (pinfunction "2_2") (pintype "passive"))
    )
    (net (code "68") (name "Net-(Q2-PadB)") (class "Default")
      (node (ref "Q2") (pin "B") (pinfunction "B_B") (pintype "passive"))
      (node (ref "R3") (pin "2") (pinfunction "2_2") (pintype "passive"))
    )
    (net (code "69") (name "Net-(Q3-PadB)") (class "Default")
      (node (ref "Q3") (pin "B") (pinfunction "B_B") (pintype "passive"))
      (node (ref "R4") (pin "2") (pinfunction "2_2") (pintype "passive"))
    )
    (net (code "70") (name "Net-(Q4-PadB)") (class "Default")
      (node (ref "Q4") (pin "B") (pinfunction "B_B") (pintype "passive"))
      (node (ref "R5") (pin "2") (pinfunction "2_2") (pintype "passive"))
    )
    (net (code "71") (name "Net-(Q5-PadB)") (class "Default")
      (node (ref "Q5") (pin "B") (pinfunction "B_B") (pintype "passive"))
      (node (ref "R6") (pin "2") (pinfunction "2_2") (pintype "passive"))
    )
    (net (code "72") (name "Net-(Q6-PadB)") (class "Default")
      (node (ref "Q6") (pin "B") (pinfunction "B_B") (pintype "passive"))
      (node (ref "R7") (pin "2") (pinfunction "2_2") (pintype "passive"))
    )
    (net (code "73") (name "Net-(Q7-PadB)") (class "Default")
      (node (ref "Q7") (pin "B") (pinfunction "B_B") (pintype "passive"))
      (node (ref "R8") (pin "2") (pinfunction "2_2") (pintype "passive"))
    )
    (net (code "74") (name "Net-(Q8-PadB)") (class "Default")
      (node (ref "Q8") (pin "B") (pinfunction "B_B") (pintype "passive"))
      (node (ref "R9") (pin "2") (pinfunction "2_2") (pintype "passive"))
    )
    (net (code "75") (name "Net-(Q9-PadB)") (class "Default")
      (node (ref "Q9") (pin "B") (pinfunction "B_B") (pintype "passive"))
      (node (ref "R10") (pin "2") (pinfunction "2_2") (pintype "passive"))
    )
    (net (code "76") (name "Net-(Q10-PadB)") (class "Default")
      (node (ref "Q10") (pin "B") (pinfunction "B_B") (pintype "passive"))
      (node (ref "R11") (pin "2") (pinfunction "2_2") (pintype "passive"))
    )
    (net (code "77") (name "Net-(Q11-PadB)") (class "Default")
      (node (ref "Q11") (pin "B") (pinfunction "B_B") (pintype "passive"))
      (node (ref "R12") (pin "2") (pinfunction "2_2") (pintype "passive"))
    )
    (net (code "78") (name "Net-(Q12-PadB)") (class "Default")
      (node (ref "Q12") (pin "B") (pinfunction "B_B") (pintype "passive"))
      (node (ref "R13") (pin "2") (pinfunction "2_2") (pintype "passive"))
    )
    (net (code "79") (name "Net-(Q13-PadB)") (class "Default")
      (node (ref "Q13") (pin "B") (pinfunction "B_B") (pintype "passive"))
      (node (ref "R14") (pin "2") (pinfunction "2_2") (pintype "passive"))
    )
    (net (code "80") (name "Net-(Q14-PadB)") (class "Default")
      (node (ref "Q14") (pin "B") (pinfunction "B_B") (pintype "passive"))
      (node (ref "R15") (pin "2") (pinfunction "2_2") (pintype "passive"))
    )
    (net (code "81") (name "Net-(Q15-PadB)") (class "Default")
      (node (ref "Q15") (pin "B") (pinfunction "B_B") (pintype "passive"))
      (node (ref "R16") (pin "2") (pinfunction "2_2") (pintype "passive"))
    )
    (net (code "82") (name "Net-(Q16-PadB)") (class "Default")
      (node (ref "Q16") (pin "B") (pinfunction "B_B") (pintype "passive"))
      (node (ref "R17") (pin "2") (pinfunction "2_2") (pintype "passive"))
    )
    (net (code "83") (name "Net-(Q17-PadB)") (class "Default")
      (node (ref "Q17") (pin "B") (pinfunction "B_B") (pintype "passive"))
      (node (ref "R1") (pin "2") (pinfunction "2_2") (pintype "passive"))
    )
    (net (code "84") (name "Net-(Q18-PadB)") (class "Default")
      (node (ref "Q18") (pin "B") (pinfunction "B_B") (pintype "passive"))
      (node (ref "R18") (pin "2") (pinfunction "2_2") (pintype "passive"))
    )
    (net (code "85") (name "Net-(Q19-PadB)") (class "Default")
      (node (ref "Q19") (pin "B") (pinfunction "B_B") (pintype "passive"))
      (node (ref "R19") (pin "2") (pinfunction "2_2") (pintype "passive"))
    )
    (net (code "86") (name "Net-(Q20-PadB)") (class "Default")
      (node (ref "Q20") (pin "B") (pinfunction "B_B") (pintype "passive"))
      (node (ref "R20") (pin "2") (pinfunction "2_2") (pintype "passive"))
    )
    (net (code "87") (name "Net-(Q21-PadB)") (class "Default")
      (node (ref "Q21") (pin "B") (pinfunction "B_B") (pintype "passive"))
      (node (ref "R21") (pin "2") (pinfunction "2_2") (pintype "passive"))
    )
    (net (code "88") (name "Net-(Q22-PadB)") (class "Default")
      (node (ref "Q22") (pin "B") (pinfunction "B_B") (pintype "passive"))
      (node (ref "R22") (pin "2") (pinfunction "2_2") (pintype "passive"))
    )
    (net (code "89") (name "Net-(Q23-PadB)") (class "Default")
      (node (ref "Q23") (pin "B") (pinfunction "B_B") (pintype "passive"))
      (node (ref "R23") (pin "2") (pinfunction "2_2") (pintype "passive"))
    )
    (net (code "90") (name "Net-(Q24-PadB)") (class "Default")
      (node (ref "Q24") (pin "B") (pinfunction "B_B") (pintype "passive"))
      (node (ref "R24") (pin "2") (pinfunction "2_2") (pintype "passive"))
    )
    (net (code "91") (name "Net-(Q25-PadB)") (class "Default")
      (node (ref "Q25") (pin "B") (pinfunction "B_B") (pintype "passive"))
      (node (ref "R25") (pin "2") (pinfunction "2_2") (pintype "passive"))
    )
    (net (code "92") (name "Net-(Q26-PadB)") (class "Default")
      (node (ref "Q26") (pin "B") (pinfunction "B_B") (pintype "passive"))
      (node (ref "R26") (pin "2") (pinfunction "2_2") (pintype "passive"))
    )
    (net (code "93") (name "Net-(Q27-PadB)") (class "Default")
      (node (ref "Q27") (pin "B") (pinfunction "B_B") (pintype "passive"))
      (node (ref "R27") (pin "2") (pinfunction "2_2") (pintype "passive"))
    )
    (net (code "94") (name "Net-(Q28-PadB)") (class "Default")
      (node (ref "Q28") (pin "B") (pinfunction "B_B") (pintype "passive"))
      (node (ref "R28") (pin "2") (pinfunction "2_2") (pintype "passive"))
    )
    (net (code "95") (name "Net-(Q29-PadB)") (class "Default")
      (node (ref "Q29") (pin "B") (pinfunction "B_B") (pintype "passive"))
      (node (ref "R29") (pin "2") (pinfunction "2_2") (pintype "passive"))
    )
    (net (code "96") (name "Net-(Q30-PadB)") (class "Default")
      (node (ref "Q30") (pin "B") (pinfunction "B_B") (pintype "passive"))
      (node (ref "R30") (pin "2") (pinfunction "2_2") (pintype "passive"))
    )
    (net (code "97") (name "Net-(Q31-PadB)") (class "Default")
      (node (ref "Q31") (pin "B") (pinfunction "B_B") (pintype "passive"))
      (node (ref "R31") (pin "2") (pinfunction "2_2") (pintype "passive"))
    )
    (net (code "98") (name "Net-(Q32-PadB)") (class "Default")
      (node (ref "Q32") (pin "B") (pinfunction "B_B") (pintype "passive"))
      (node (ref "R32") (pin "2") (pinfunction "2_2") (pintype "passive"))
    )
    (net (code "99") (name "Net-(U$1-IO2)") (class "Default")
      (node (ref "RELAY_BAR") (pin "8") (pinfunction "8_8") (pintype "passive"))
      (node (ref "U$1") (pin "4") (pinfunction "IO2_4") (pintype "bidirectional"))
    )
    (net (code "100") (name "Net-(U$1-IO4)") (class "Default")
      (node (ref "RELAY_BAR") (pin "7") (pinfunction "7_7") (pintype "passive"))
      (node (ref "U$1") (pin "5") (pinfunction "IO4_5") (pintype "bidirectional"))
    )
    (net (code "101") (name "Net-(U$1-IO5)") (class "Default")
      (node (ref "RELAY_BAR") (pin "4") (pinfunction "4_4") (pintype "passive"))
      (node (ref "U$1") (pin "8") (pinfunction "IO5_8") (pintype "bidirectional"))
    )
    (net (code "102") (name "Net-(U$1-IO15)") (class "Default")
      (node (ref "RELAY_BAR") (pin "9") (pinfunction "9_9") (pintype "passive"))
      (node (ref "U$1") (pin "3") (pinfunction "IO15_3") (pintype "bidirectional"))
    )
    (net (code "103") (name "Net-(U$1-IO16)") (class "Default")
      (node (ref "RELAY_BAR") (pin "6") (pinfunction "6_6") (pintype "passive"))
      (node (ref "U$1") (pin "6") (pinfunction "IO16_6") (pintype "bidirectional"))
    )
    (net (code "104") (name "Net-(U$1-IO17)") (class "Default")
      (node (ref "RELAY_BAR") (pin "5") (pinfunction "5_5") (pintype "passive"))
      (node (ref "U$1") (pin "7") (pinfunction "IO17_7") (pintype "bidirectional"))
    )
    (net (code "105") (name "Net-(U$1-IO18)") (class "Default")
      (node (ref "RELAY_BAR") (pin "3") (pinfunction "3_3") (pintype "passive"))
      (node (ref "U$1") (pin "9") (pinfunction "IO18_9") (pintype "bidirectional"))
    )
    (net (code "106") (name "Net-(U$1-IO19)") (class "Default")
      (node (ref "RELAY_BAR") (pin "2") (pinfunction "2_2") (pintype "passive"))
      (node (ref "U$1") (pin "10") (pinfunction "IO19_10") (pintype "bidirectional"))
    )
    (net (code "107") (name "Net-(U$1-IO21)") (class "Default")
      (node (ref "I2C-PWM") (pin "4") (pinfunction "4_4") (pintype "passive"))
      (node (ref "I2C-PWM1") (pin "4") (pinfunction "4_4") (pintype "passive"))
      (node (ref "U$1") (pin "11") (pinfunction "IO21_11") (pintype "bidirectional"))
    )
    (net (code "108") (name "Net-(U$1-IO22)") (class "Default")
      (node (ref "I2C-PWM") (pin "3") (pinfunction "3_3") (pintype "passive"))
      (node (ref "I2C-PWM1") (pin "3") (pinfunction "3_3") (pintype "passive"))
      (node (ref "U$1") (pin "14") (pinfunction "IO22_14") (pintype "bidirectional"))
    )
    (net (code "109") (name "Net-(U$1-VIN)") (class "Default")
      (node (ref "I2C-PWM") (pin "5") (pinfunction "5_5") (pintype "passive"))
      (node (ref "I2C-PWM1") (pin "5") (pinfunction "5_5") (pintype "passive"))
      (node (ref "RELAY_BAR") (pin "10") (pinfunction "10_10") (pintype "passive"))
      (node (ref "U$1") (pin "30") (pinfunction "VIN_30") (pintype "bidirectional"))
      (node (ref "X1") (pin "4") (pinfunction "S_4") (pintype "passive"))
    )
    (net (code "110") (name "unconnected-(I2C-PWM-Pad2)") (class "Default")
      (node (ref "I2C-PWM") (pin "2") (pinfunction "2_2") (pintype "passive"))
    )
    (net (code "111") (name "unconnected-(I2C-PWM-Pad6)") (class "Default")
      (node (ref "I2C-PWM") (pin "6") (pinfunction "6_6") (pintype "passive"))
    )
    (net (code "112") (name "unconnected-(I2C-PWM1-Pad2)") (class "Default")
      (node (ref "I2C-PWM1") (pin "2") (pinfunction "2_2") (pintype "passive"))
    )
    (net (code "113") (name "unconnected-(I2C-PWM1-Pad6)") (class "Default")
      (node (ref "I2C-PWM1") (pin "6") (pinfunction "6_6") (pintype "passive"))
    )
    (net (code "114") (name "unconnected-(U$1-3V3-Pad1)") (class "Default")
      (node (ref "U$1") (pin "1") (pinfunction "3V3_1") (pintype "bidirectional"))
    )
    (net (code "115") (name "unconnected-(U$1-EN-Pad16)") (class "Default")
      (node (ref "U$1") (pin "16") (pinfunction "EN_16") (pintype "bidirectional"))
    )
    (net (code "116") (name "unconnected-(U$1-GND1-Pad28)") (class "Default")
      (node (ref "U$1") (pin "28") (pinfunction "GND1_28") (pintype "bidirectional"))
    )
    (net (code "117") (name "unconnected-(U$1-IO1-Pad13)") (class "Default")
      (node (ref "U$1") (pin "13") (pinfunction "IO1_13") (pintype "bidirectional"))
    )
    (net (code "118") (name "unconnected-(U$1-IO3-Pad12)") (class "Default")
      (node (ref "U$1") (pin "12") (pinfunction "IO3_12") (pintype "bidirectional"))
    )
    (net (code "119") (name "unconnected-(U$1-IO12-Pad27)") (class "Default")
      (node (ref "U$1") (pin "27") (pinfunction "IO12_27") (pintype "bidirectional"))
    )
    (net (code "120") (name "unconnected-(U$1-IO13-Pad28)") (class "Default")
      (node (ref "U$1") (pin "28") (pinfunction "IO13_28") (pintype "bidirectional"))
    )
    (net (code "121") (name "unconnected-(U$1-IO14-Pad26)") (class "Default")
      (node (ref "U$1") (pin "26") (pinfunction "IO14_26") (pintype "bidirectional"))
    )
    (net (code "122") (name "unconnected-(U$1-IO23-Pad15)") (class "Default")
      (node (ref "U$1") (pin "15") (pinfunction "IO23_15") (pintype "bidirectional"))
    )
    (net (code "123") (name "unconnected-(U$1-IO25-Pad23)") (class "Default")
      (node (ref "U$1") (pin "23") (pinfunction "IO25_23") (pintype "bidirectional"))
    )
    (net (code "124") (name "unconnected-(U$1-IO26-Pad24)") (class "Default")
      (node (ref "U$1") (pin "24") (pinfunction "IO26_24") (pintype "bidirectional"))
    )
    (net (code "125") (name "unconnected-(U$1-IO27-Pad24)") (class "Default")
      (node (ref "U$1") (pin "24") (pinfunction "IO27_24") (pintype "bidirectional"))
    )
    (net (code "126") (name "unconnected-(U$1-IO32-Pad21)") (class "Default")
      (node (ref "U$1") (pin "21") (pinfunction "IO32_21") (pintype "bidirectional"))
    )
    (net (code "127") (name "unconnected-(U$1-IO33-Pad22)") (class "Default")
      (node (ref "U$1") (pin "22") (pinfunction "IO33_22") (pintype "bidirectional"))
    )
    (net (code "128") (name "unconnected-(U$1-IO34-Pad19)") (class "Default")
      (node (ref "U$1") (pin "19") (pinfunction "IO34_19") (pintype "bidirectional"))
    )
    (net (code "129") (name "unconnected-(U$1-IO35-Pad20)") (class "Default")
      (node (ref "U$1") (pin "20") (pinfunction "IO35_20") (pintype "bidirectional"))
    )
    (net (code "130") (name "unconnected-(U$1-VN-Pad18)") (class "Default")
      (node (ref "U$1") (pin "18") (pinfunction "VN_18") (pintype "bidirectional"))
    )
    (net (code "131") (name "unconnected-(U$1-VP-Pad17)") (class "Default")
      (node (ref "U$1") (pin "17") (pinfunction "VP_17") (pintype "bidirectional"))
    )
  )
)
